# SCH_sensors_2026-04-29.net
KiCad netlist of a schematic drawn in EasyEDA
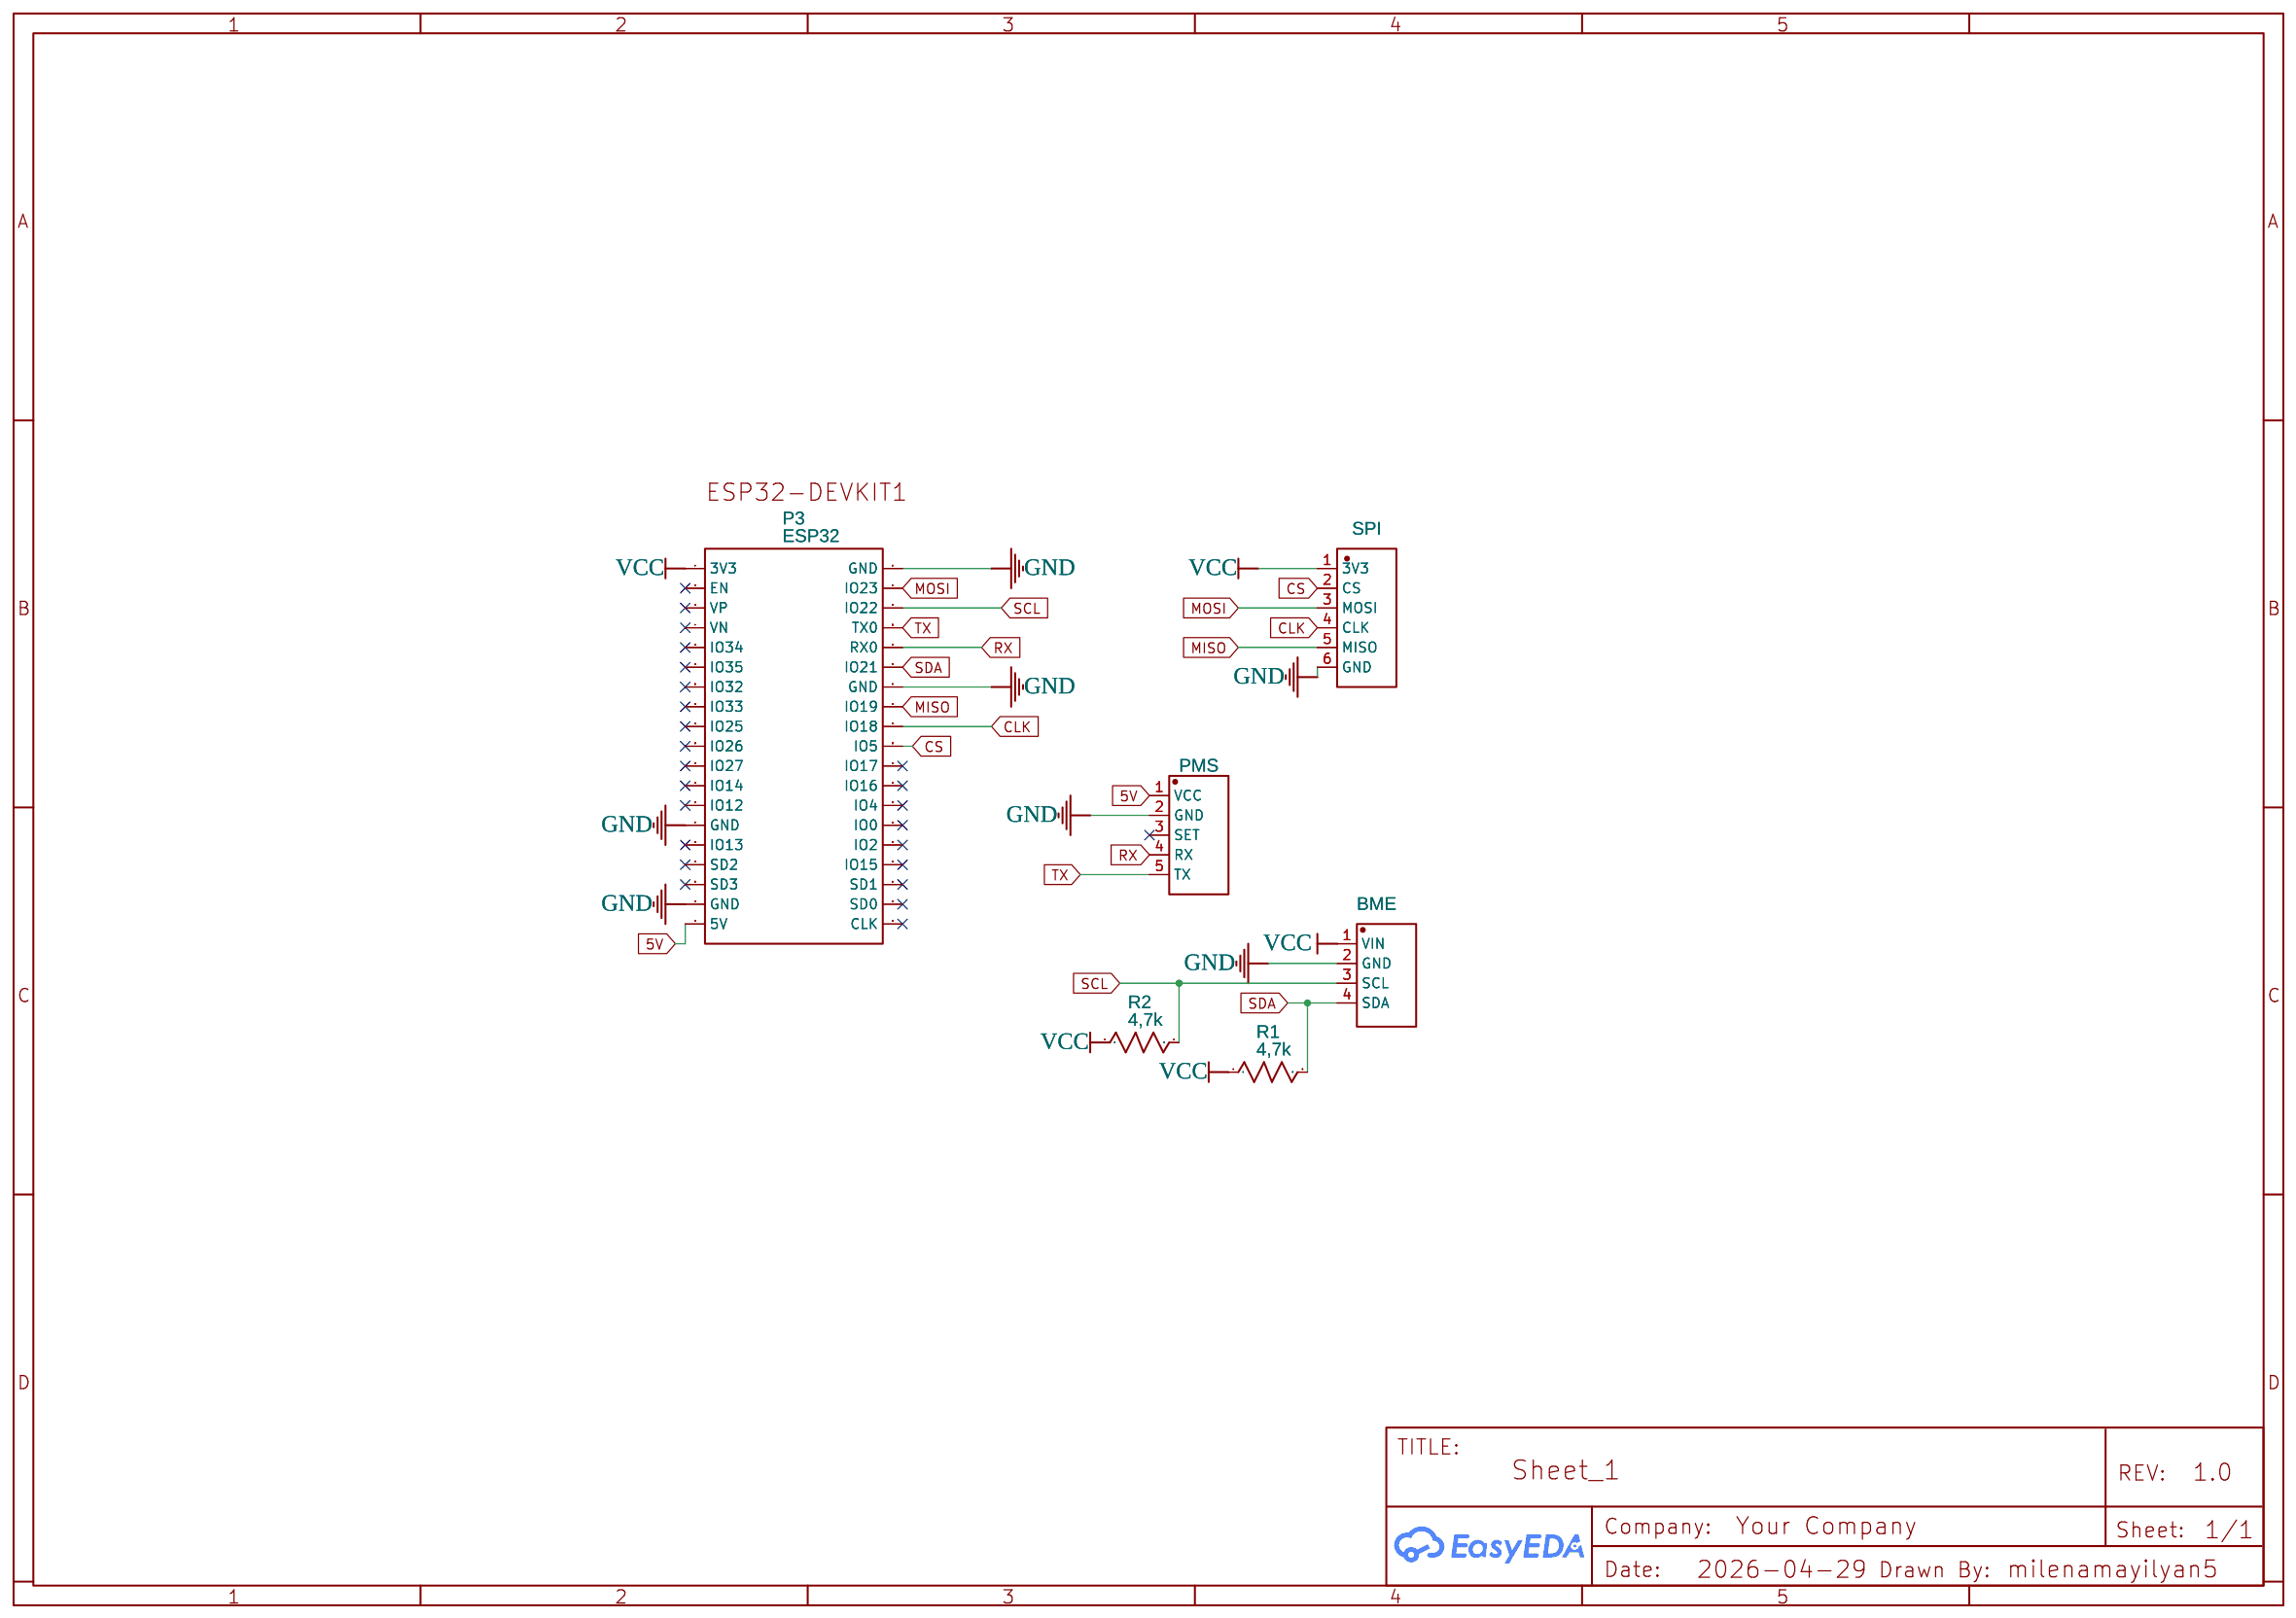
[diagram p0: schematic sheet]

(export (version "E")
  (design (tool "Eeschema 10.0.6"))
  (components
    (comp (ref "BME") (value "I2C RAIL COPY") (libsource (lib "") (part "I2C RAIL COPY")))
    (comp (ref "BME1") (value "SPI") (libsource (lib "") (part "header male L298N 1x6 2.54")))
    (comp (ref "P3")
      (value "ESP32")
      (fields
        (field (name "Manufacturer Part") "Header-Male-2.54_2x19")
        (field (name "Manufacturer") "ReliaPro")
      )
      (libsource (lib "") (part "ESP32"))
    )
    (comp (ref "PMS") (value "HEADER - 2.54_1X5") (libsource (lib "") (part "HEADER - 2.54_1X5")))
    (comp (ref "R1") (value "4,7k") (libsource (lib "") (part "R_0603_US")))
    (comp (ref "R2") (value "4,7k") (libsource (lib "") (part "R_0603_US")))
  )
  (nets
    (net (code "1") (name "5V") (class "Default")
      (node (ref "P3") (pin "37") (pinfunction "5V_37") (pintype "input"))
      (node (ref "PMS") (pin "1") (pinfunction "VCC_1") (pintype "unspecified"))
    )
    (net (code "2") (name "CLK") (class "Default")
      (node (ref "BME1") (pin "4") (pinfunction "CLK_4") (pintype "unspecified"))
      (node (ref "P3") (pin "18") (pinfunction "IO18_18") (pintype "input"))
    )
    (net (code "3") (name "CS") (class "Default")
      (node (ref "BME1") (pin "2") (pinfunction "CS_2") (pintype "unspecified"))
      (node (ref "P3") (pin "20") (pinfunction "IO5_20") (pintype "input"))
    )
    (net (code "4") (name "GND") (class "Default")
      (node (ref "BME") (pin "2") (pinfunction "GND_2") (pintype "unspecified"))
      (node (ref "BME1") (pin "6") (pinfunction "GND_6") (pintype "unspecified"))
      (node (ref "P3") (pin "14") (pinfunction "GND_14") (pintype "input"))
      (node (ref "P3") (pin "2") (pinfunction "GND_2") (pintype "input"))
      (node (ref "P3") (pin "27") (pinfunction "GND_27") (pintype "input"))
      (node (ref "P3") (pin "35") (pinfunction "GND_35") (pintype "input"))
      (node (ref "PMS") (pin "2") (pinfunction "GND_2") (pintype "unspecified"))
    )
    (net (code "5") (name "MISO") (class "Default")
      (node (ref "BME1") (pin "5") (pinfunction "MISO_5") (pintype "unspecified"))
      (node (ref "P3") (pin "16") (pinfunction "IO19_16") (pintype "input"))
    )
    (net (code "6") (name "MOSI") (class "Default")
      (node (ref "BME1") (pin "3") (pinfunction "MOSI_3") (pintype "unspecified"))
      (node (ref "P3") (pin "4") (pinfunction "IO23_4") (pintype "input"))
    )
    (net (code "7") (name "RX") (class "Default")
      (node (ref "P3") (pin "10") (pinfunction "RX0_10") (pintype "input"))
      (node (ref "PMS") (pin "4") (pinfunction "RX_4") (pintype "unspecified"))
    )
    (net (code "8") (name "SCL") (class "Default")
      (node (ref "BME") (pin "3") (pinfunction "SCL_3") (pintype "unspecified"))
      (node (ref "P3") (pin "6") (pinfunction "IO22_6") (pintype "input"))
      (node (ref "R2") (pin "2") (pinfunction "2_2") (pintype "unspecified"))
    )
    (net (code "9") (name "SDA") (class "Default")
      (node (ref "BME") (pin "4") (pinfunction "SDA_4") (pintype "unspecified"))
      (node (ref "P3") (pin "12") (pinfunction "IO21_12") (pintype "input"))
      (node (ref "R1") (pin "2") (pinfunction "2_2") (pintype "unspecified"))
    )
    (net (code "10") (name "TX") (class "Default")
      (node (ref "P3") (pin "8") (pinfunction "TX0_8") (pintype "input"))
      (node (ref "PMS") (pin "5") (pinfunction "TX_5") (pintype "unspecified"))
    )
    (net (code "11") (name "VCC") (class "Default")
      (node (ref "BME") (pin "1") (pinfunction "VIN_1") (pintype "unspecified"))
      (node (ref "BME1") (pin "1") (pinfunction "3V3_1") (pintype "unspecified"))
      (node (ref "P3") (pin "1") (pinfunction "3V3_1") (pintype "input"))
      (node (ref "R1") (pin "1") (pinfunction "1_1") (pintype "unspecified"))
      (node (ref "R2") (pin "1") (pinfunction "1_1") (pintype "unspecified"))
    )
    (net (code "12") (name "unconnected-(P3-CLK-Pad38)") (class "Default")
      (node (ref "P3") (pin "38") (pinfunction "CLK_38") (pintype "input+no_connect"))
    )
    (net (code "13") (name "unconnected-(P3-EN-Pad3)") (class "Default")
      (node (ref "P3") (pin "3") (pinfunction "EN_3") (pintype "input+no_connect"))
    )
    (net (code "14") (name "unconnected-(P3-IO0-Pad28)") (class "Default")
      (node (ref "P3") (pin "28") (pinfunction "IO0_28") (pintype "input+no_connect"))
    )
    (net (code "15") (name "unconnected-(P3-IO2-Pad30)") (class "Default")
      (node (ref "P3") (pin "30") (pinfunction "IO2_30") (pintype "input+no_connect"))
    )
    (net (code "16") (name "unconnected-(P3-IO4-Pad26)") (class "Default")
      (node (ref "P3") (pin "26") (pinfunction "IO4_26") (pintype "input+no_connect"))
    )
    (net (code "17") (name "unconnected-(P3-IO12-Pad25)") (class "Default")
      (node (ref "P3") (pin "25") (pinfunction "IO12_25") (pintype "input+no_connect"))
    )
    (net (code "18") (name "unconnected-(P3-IO13-Pad29)") (class "Default")
      (node (ref "P3") (pin "29") (pinfunction "IO13_29") (pintype "input+no_connect"))
    )
    (net (code "19") (name "unconnected-(P3-IO14-Pad23)") (class "Default")
      (node (ref "P3") (pin "23") (pinfunction "IO14_23") (pintype "input+no_connect"))
    )
    (net (code "20") (name "unconnected-(P3-IO15-Pad32)") (class "Default")
      (node (ref "P3") (pin "32") (pinfunction "IO15_32") (pintype "input+no_connect"))
    )
    (net (code "21") (name "unconnected-(P3-IO16-Pad24)") (class "Default")
      (node (ref "P3") (pin "24") (pinfunction "IO16_24") (pintype "input+no_connect"))
    )
    (net (code "22") (name "unconnected-(P3-IO17-Pad22)") (class "Default")
      (node (ref "P3") (pin "22") (pinfunction "IO17_22") (pintype "input+no_connect"))
    )
    (net (code "23") (name "unconnected-(P3-IO25-Pad17)") (class "Default")
      (node (ref "P3") (pin "17") (pinfunction "IO25_17") (pintype "input+no_connect"))
    )
    (net (code "24") (name "unconnected-(P3-IO26-Pad19)") (class "Default")
      (node (ref "P3") (pin "19") (pinfunction "IO26_19") (pintype "input+no_connect"))
    )
    (net (code "25") (name "unconnected-(P3-IO27-Pad21)") (class "Default")
      (node (ref "P3") (pin "21") (pinfunction "IO27_21") (pintype "input+no_connect"))
    )
    (net (code "26") (name "unconnected-(P3-IO32-Pad13)") (class "Default")
      (node (ref "P3") (pin "13") (pinfunction "IO32_13") (pintype "input+no_connect"))
    )
    (net (code "27") (name "unconnected-(P3-IO33-Pad15)") (class "Default")
      (node (ref "P3") (pin "15") (pinfunction "IO33_15") (pintype "input+no_connect"))
    )
    (net (code "28") (name "unconnected-(P3-IO34-Pad9)") (class "Default")
      (node (ref "P3") (pin "9") (pinfunction "IO34_9") (pintype "input+no_connect"))
    )
    (net (code "29") (name "unconnected-(P3-IO35-Pad11)") (class "Default")
      (node (ref "P3") (pin "11") (pinfunction "IO35_11") (pintype "input+no_connect"))
    )
    (net (code "30") (name "unconnected-(P3-SD0-Pad36)") (class "Default")
      (node (ref "P3") (pin "36") (pinfunction "SD0_36") (pintype "input+no_connect"))
    )
    (net (code "31") (name "unconnected-(P3-SD1-Pad34)") (class "Default")
      (node (ref "P3") (pin "34") (pinfunction "SD1_34") (pintype "input+no_connect"))
    )
    (net (code "32") (name "unconnected-(P3-SD2-Pad31)") (class "Default")
      (node (ref "P3") (pin "31") (pinfunction "SD2_31") (pintype "input+no_connect"))
    )
    (net (code "33") (name "unconnected-(P3-SD3-Pad33)") (class "Default")
      (node (ref "P3") (pin "33") (pinfunction "SD3_33") (pintype "input+no_connect"))
    )
    (net (code "34") (name "unconnected-(P3-VN-Pad7)") (class "Default")
      (node (ref "P3") (pin "7") (pinfunction "VN_7") (pintype "input+no_connect"))
    )
    (net (code "35") (name "unconnected-(P3-VP-Pad5)") (class "Default")
      (node (ref "P3") (pin "5") (pinfunction "VP_5") (pintype "input+no_connect"))
    )
    (net (code "36") (name "unconnected-(PMS-SET-Pad3)") (class "Default")
      (node (ref "PMS") (pin "3") (pinfunction "SET_3") (pintype "unspecified+no_connect"))
    )
  )
)
